# vaja_1_2.net
KiCad netlist of a schematic drawn in Altium Designer
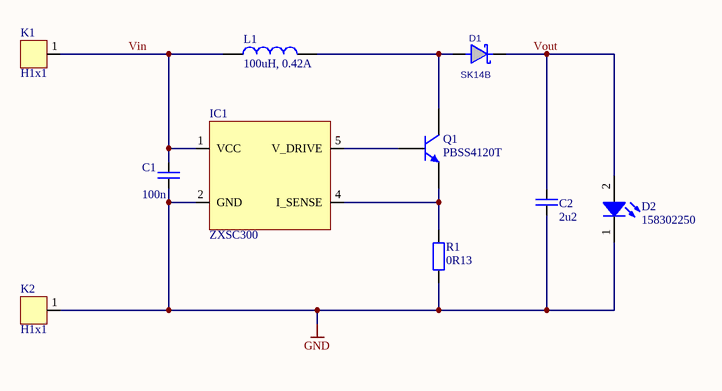
[diagram p0: vaja_1_2.SchDoc]

(export (version "E")
  (design (tool "Eeschema 10.0.6"))
  (components
    (comp (ref "C1")
      (value "100n")
      (footprint "CAP 0805_2012")
      (description "Capacitor")
      (libsource (lib "General") (part "C"))
    )
    (comp (ref "C2")
      (value "2u2")
      (footprint "CAP 0805_2012")
      (description "Capacitor")
      (libsource (lib "General") (part "C"))
    )
    (comp (ref "D1")
      (value "SK14B")
      (footprint "DO-214AA")
      (description "Schottky")
      (libsource (lib "vaja_1_lib") (part "SK14B"))
    )
    (comp (ref "D2")
      (value "158302250")
      (footprint "WL-SWTP_3022")
      (description "WL-SWTP SMT White Top view PLCC, size 3022, Daylight, 3.2V, 120deg")
      (fields (field (name "MANUFACTURER") "Wurth Elektronik"))
      (libsource (lib "WL-SWTP (rev21a) (1)") (part "158302250"))
    )
    (comp (ref "IC1")
      (value "ZXSC300")
      (footprint "SOT23-5")
      (description "Led driver IC")
      (libsource (lib "vaja_1_lib") (part "ZXSC300"))
    )
    (comp (ref "K1")
      (value "H1x1")
      (footprint "HDR1X1")
      (description "Header 1x1 (male)")
      (libsource (lib "Kon_Tipk") (part "H1x1"))
    )
    (comp (ref "K2")
      (value "H1x1")
      (footprint "HDR1X1")
      (description "Header 1x1 (male)")
      (libsource (lib "Kon_Tipk") (part "H1x1"))
    )
    (comp (ref "L1")
      (value "100uH, 0.42A")
      (footprint "WE-LQFS_4818")
      (description "WE-LQFS SMT Power Inductor, size 4818, 100uH, 0.42A")
      (fields
        (field (name "MANUFACTURER") "Wurth Elektronik")
        (field (name "MANUFACTURER PART NUMBER") "74406042101")
      )
      (libsource (lib "Altium_WE-LQFS (rev20a) (1)") (part "74406042101"))
    )
    (comp (ref "Q1")
      (value "PBSS4120T")
      (footprint "SOT23_N")
      (description "NPN Bipolar Transistor")
      (fields (field (name "PUBLISHER") "Altium Limited"))
      (libsource (lib "Miscellaneous Devices") (part "NPN"))
    )
    (comp (ref "R1")
      (value "0R13")
      (footprint "RES 0805_2012")
      (description "R")
      (libsource (lib "General") (part "R"))
    )
  )
  (nets
    (net (code "1") (name "/Vin") (class "Default")
      (node (ref "C1") (pin "1") (pinfunction "1_1") (pintype "passive"))
      (node (ref "IC1") (pin "1") (pinfunction "VCC_1") (pintype "passive"))
      (node (ref "K1") (pin "1") (pinfunction "1_1") (pintype "passive"))
      (node (ref "L1") (pin "1") (pinfunction "1_1") (pintype "passive"))
    )
    (net (code "2") (name "/Vout") (class "Default")
      (node (ref "C2") (pin "1") (pinfunction "1_1") (pintype "passive"))
      (node (ref "D1") (pin "1") (pinfunction "K_1") (pintype "passive"))
      (node (ref "D2") (pin "2") (pinfunction "A_2") (pintype "passive"))
    )
    (net (code "3") (name "GND") (class "Default")
      (node (ref "C1") (pin "2") (pinfunction "2_2") (pintype "passive"))
      (node (ref "C2") (pin "2") (pinfunction "2_2") (pintype "passive"))
      (node (ref "D2") (pin "1") (pinfunction "K_1") (pintype "passive"))
      (node (ref "IC1") (pin "2") (pinfunction "GND_2") (pintype "passive"))
      (node (ref "K2") (pin "1") (pinfunction "1_1") (pintype "passive"))
      (node (ref "R1") (pin "2") (pintype "passive"))
    )
    (net (code "4") (name "Net-(D1-A)") (class "Default")
      (node (ref "D1") (pin "2") (pinfunction "A_2") (pintype "passive"))
      (node (ref "L1") (pin "2") (pinfunction "2_2") (pintype "passive"))
      (node (ref "Q1") (pin "1") (pinfunction "C_1") (pintype "passive"))
    )
    (net (code "5") (name "Net-(IC1-I_SENSE)") (class "Default")
      (node (ref "IC1") (pin "4") (pinfunction "I_SENSE_4") (pintype "passive"))
      (node (ref "Q1") (pin "3") (pinfunction "E_3") (pintype "passive"))
      (node (ref "R1") (pin "1") (pintype "passive"))
    )
    (net (code "6") (name "Net-(IC1-V_DRIVE)") (class "Default")
      (node (ref "IC1") (pin "5") (pinfunction "V_DRIVE_5") (pintype "passive"))
      (node (ref "Q1") (pin "2") (pinfunction "B_2") (pintype "passive"))
    )
  )
)
